# RTC.net
KiCad netlist of a schematic drawn in Altium Designer
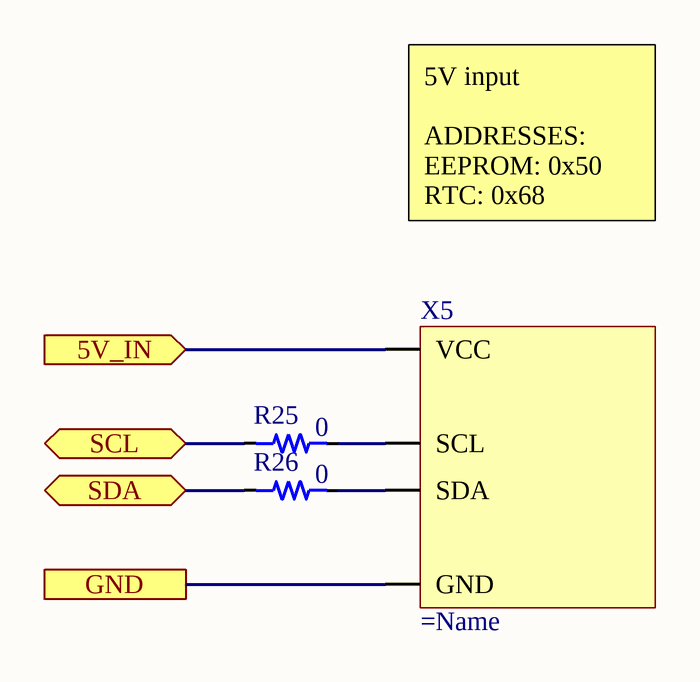
[diagram p0: RTC.SchDoc]

(export (version "E")
  (design (tool "Eeschema 10.0.6"))
  (components
    (comp (ref "R25")
      (value "0")
      (footprint "0603_RES")
      (fields (field (name "Comment") "Resistor"))
      (libsource (lib "Resistors") (part "Resistor"))
    )
    (comp (ref "R26")
      (value "0")
      (footprint "0603_RES")
      (fields (field (name "Comment") "Resistor"))
      (libsource (lib "Resistors") (part "Resistor"))
    )
    (comp (ref "X5")
      (value "~")
      (footprint "RTC Module Generic")
      (description "Generic RTC module with DS3231 and AT24C32")
      (libsource (lib "Modules") (part "RTC Module"))
    )
  )
  (nets
    (net (code "1") (name "/5V_IN") (class "Default")
      (node (ref "X5") (pin "2") (pinfunction "VCC_2") (pintype "passive"))
    )
    (net (code "2") (name "/GND") (class "Default")
      (node (ref "X5") (pin "1") (pinfunction "GND_1") (pintype "passive"))
    )
    (net (code "3") (name "/SCL") (class "Default")
      (node (ref "R25") (pin "1") (pinfunction "1_1") (pintype "passive"))
    )
    (net (code "4") (name "/SDA") (class "Default")
      (node (ref "R26") (pin "1") (pinfunction "1_1") (pintype "passive"))
    )
    (net (code "5") (name "Net-(X5-SCL)") (class "Default")
      (node (ref "R25") (pin "2") (pinfunction "2_2") (pintype "passive"))
      (node (ref "X5") (pin "4") (pinfunction "SCL_4") (pintype "passive"))
    )
    (net (code "6") (name "Net-(X5-SDA)") (class "Default")
      (node (ref "R26") (pin "2") (pinfunction "2_2") (pintype "passive"))
      (node (ref "X5") (pin "3") (pinfunction "SDA_3") (pintype "passive"))
    )
  )
)
